# AcquisitionAnalog.net
KiCad netlist of a schematic drawn in Altium Designer
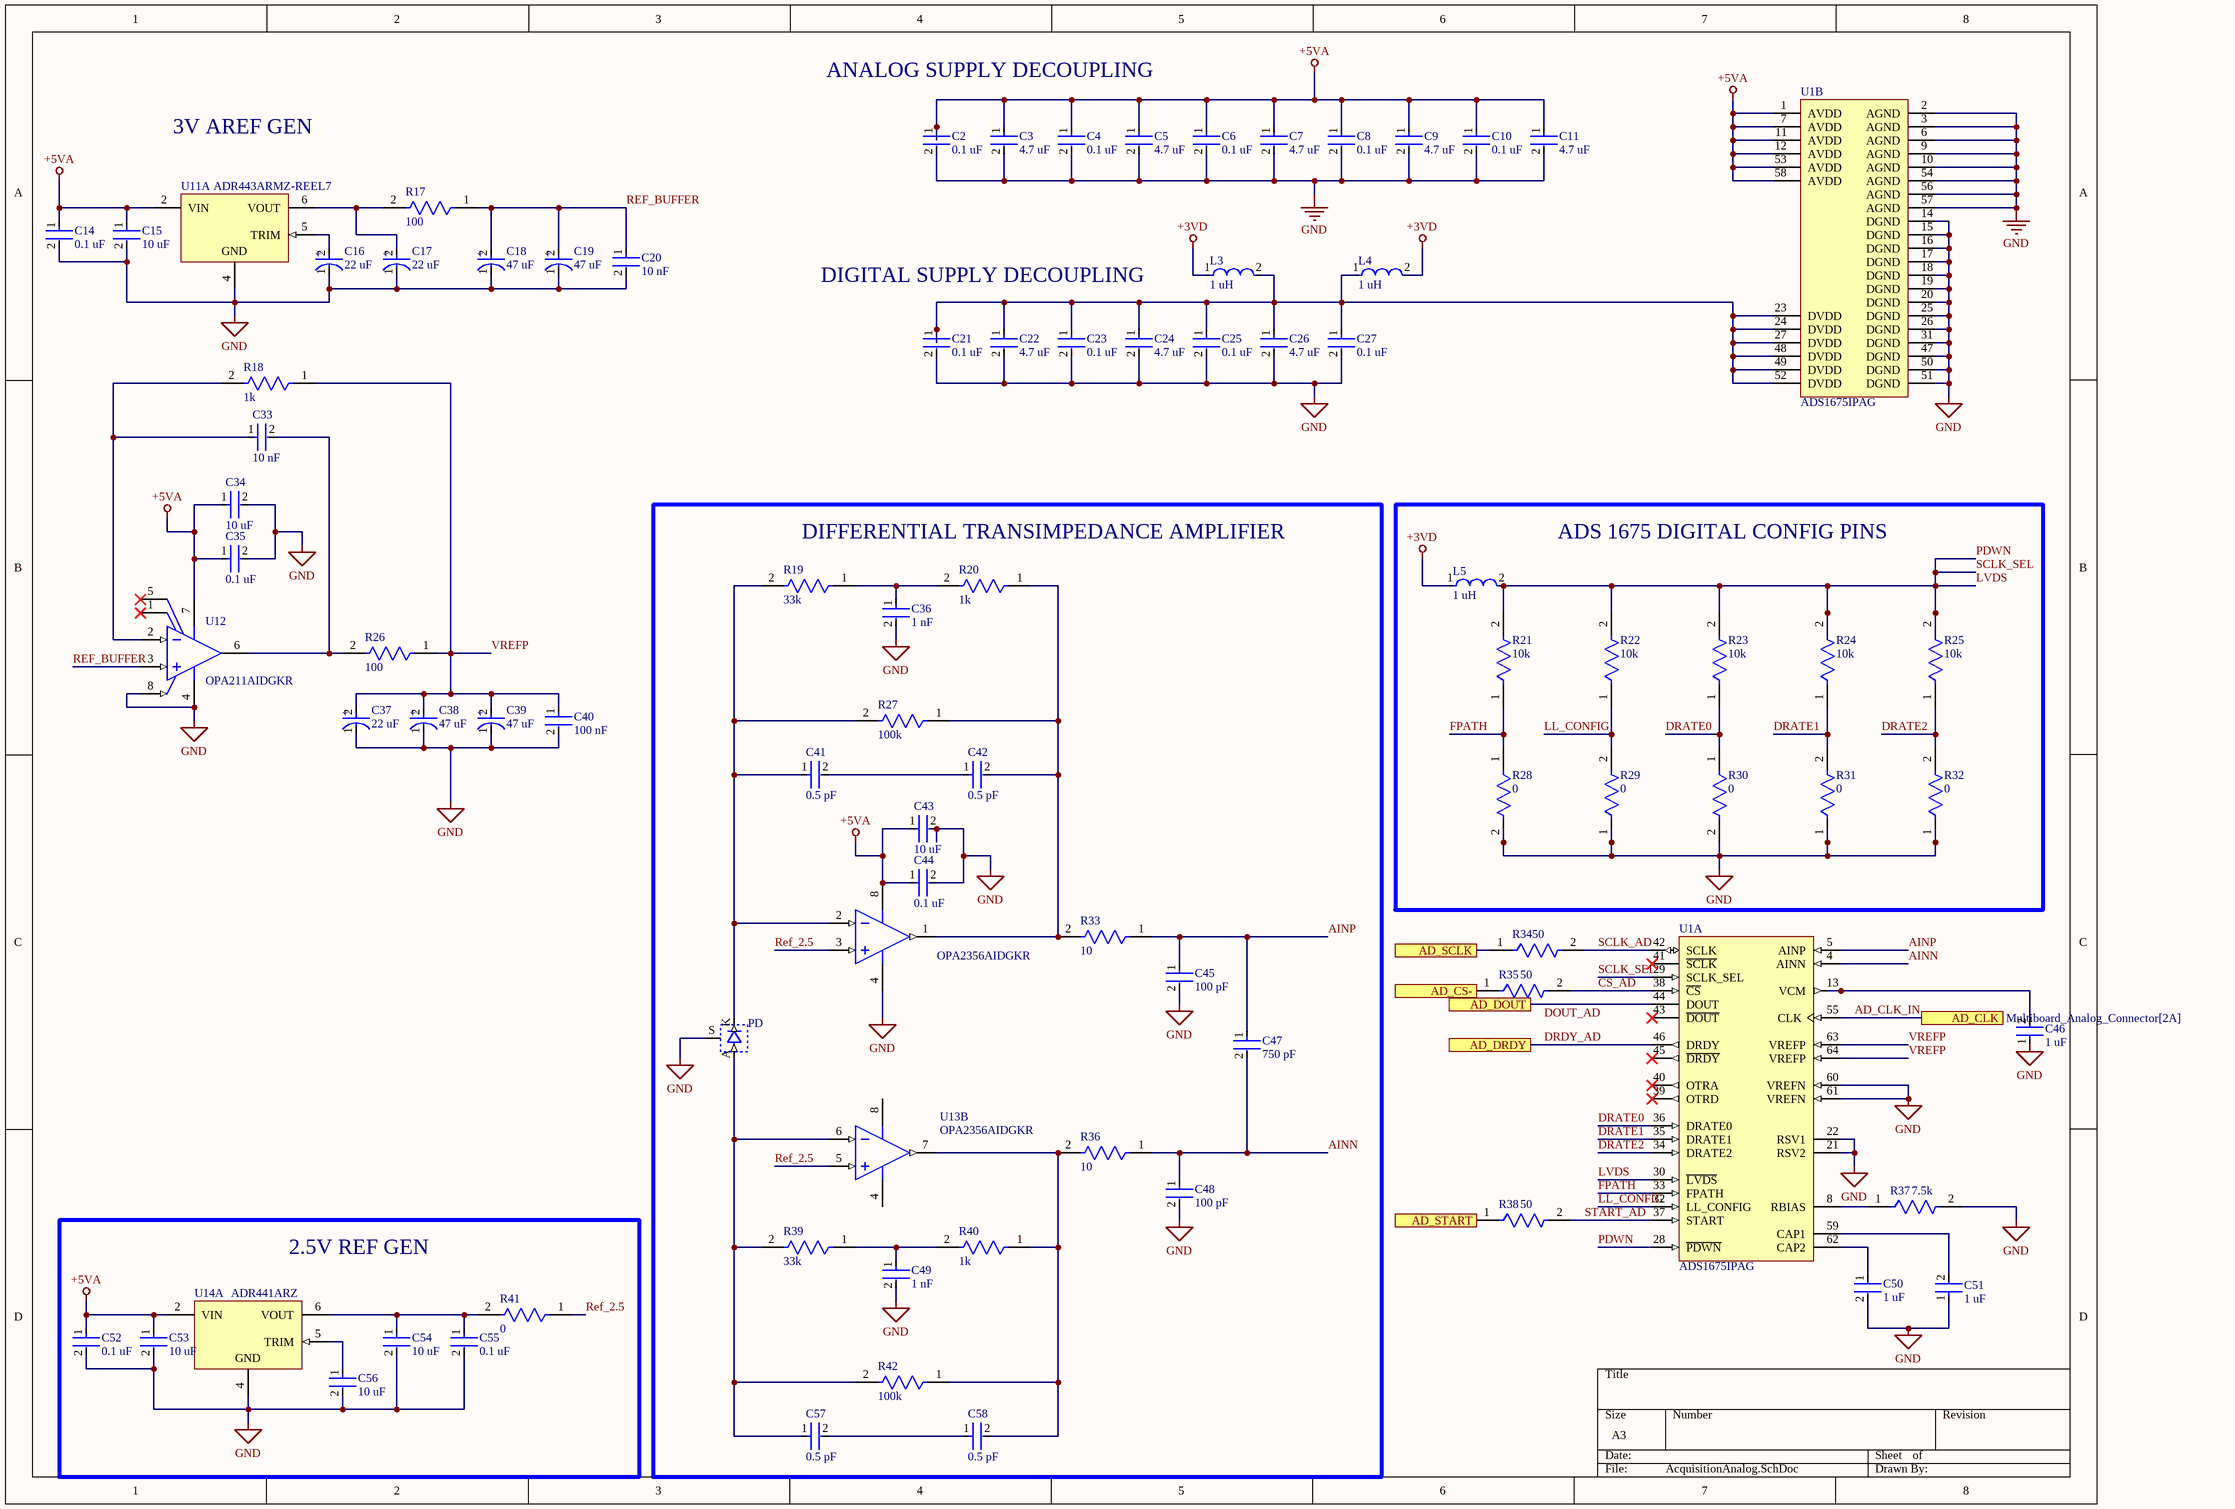
[diagram p0: AcquisitionAnalog.SchDoc]

(export (version "E")
  (design (tool "Eeschema 10.0.6"))
  (components
    (comp (ref "C2")
      (value "0.1 uF")
      (footprint "FP-CC0805-0_85-MFG")
      (description "CAP CER 0.1UF 25V X7R 0805")
      (fields (field (name "MANUFACTURER PART NUMBER") "CC0805KRX7R8BB104") (field (name "TOLERANCE") "0.1"))
      (libsource (lib "Altium Content Vault") (part "11868f565c42a9108669ba33697ecf6"))
    )
    (comp (ref "C3")
      (value "4.7 uF")
      (footprint "FP-CC0805-0_85-MFG")
      (description "CAP CER 0.1UF 25V X7R 0805")
      (fields (field (name "MANUFACTURER PART NUMBER") "CC0805KRX7R8BB104") (field (name "TOLERANCE") "0.1"))
      (libsource (lib "Altium Content Vault") (part "11868f565c42a9108669ba33697ecf6"))
    )
    (comp (ref "C4")
      (value "0.1 uF")
      (footprint "FP-CC0805-0_85-MFG")
      (description "CAP CER 0.1UF 25V X7R 0805")
      (fields (field (name "MANUFACTURER PART NUMBER") "CC0805KRX7R8BB104") (field (name "TOLERANCE") "0.1"))
      (libsource (lib "Altium Content Vault") (part "11868f565c42a9108669ba33697ecf6"))
    )
    (comp (ref "C5")
      (value "4.7 uF")
      (footprint "FP-CC0805-0_85-MFG")
      (description "CAP CER 0.1UF 25V X7R 0805")
      (fields (field (name "MANUFACTURER PART NUMBER") "CC0805KRX7R8BB104") (field (name "TOLERANCE") "0.1"))
      (libsource (lib "Altium Content Vault") (part "11868f565c42a9108669ba33697ecf6"))
    )
    (comp (ref "C6")
      (value "0.1 uF")
      (footprint "FP-CC0805-0_85-MFG")
      (description "CAP CER 0.1UF 25V X7R 0805")
      (fields (field (name "MANUFACTURER PART NUMBER") "CC0805KRX7R8BB104") (field (name "TOLERANCE") "0.1"))
      (libsource (lib "Altium Content Vault") (part "11868f565c42a9108669ba33697ecf6"))
    )
    (comp (ref "C7")
      (value "4.7 uF")
      (footprint "FP-CC0805-0_85-MFG")
      (description "CAP CER 0.1UF 25V X7R 0805")
      (fields (field (name "MANUFACTURER PART NUMBER") "CC0805KRX7R8BB104") (field (name "TOLERANCE") "0.1"))
      (libsource (lib "Altium Content Vault") (part "11868f565c42a9108669ba33697ecf6"))
    )
    (comp (ref "C8")
      (value "0.1 uF")
      (footprint "FP-CC0805-0_85-MFG")
      (description "CAP CER 0.1UF 25V X7R 0805")
      (fields (field (name "MANUFACTURER PART NUMBER") "CC0805KRX7R8BB104") (field (name "TOLERANCE") "0.1"))
      (libsource (lib "Altium Content Vault") (part "11868f565c42a9108669ba33697ecf6"))
    )
    (comp (ref "C9")
      (value "4.7 uF")
      (footprint "FP-CC0805-0_85-MFG")
      (description "CAP CER 0.1UF 25V X7R 0805")
      (fields (field (name "MANUFACTURER PART NUMBER") "CC0805KRX7R8BB104") (field (name "TOLERANCE") "0.1"))
      (libsource (lib "Altium Content Vault") (part "11868f565c42a9108669ba33697ecf6"))
    )
    (comp (ref "C10")
      (value "0.1 uF")
      (footprint "FP-CC0805-0_85-MFG")
      (description "CAP CER 0.1UF 25V X7R 0805")
      (fields (field (name "MANUFACTURER PART NUMBER") "CC0805KRX7R8BB104") (field (name "TOLERANCE") "0.1"))
      (libsource (lib "Altium Content Vault") (part "11868f565c42a9108669ba33697ecf6"))
    )
    (comp (ref "C11")
      (value "4.7 uF")
      (footprint "FP-CC0805-0_85-MFG")
      (description "CAP CER 0.1UF 25V X7R 0805")
      (fields (field (name "MANUFACTURER PART NUMBER") "CC0805KRX7R8BB104") (field (name "TOLERANCE") "0.1"))
      (libsource (lib "Altium Content Vault") (part "11868f565c42a9108669ba33697ecf6"))
    )
    (comp (ref "C14")
      (value "0.1 uF")
      (footprint "FP-CC0805-0_85-MFG")
      (description "CAP CER 0.1UF 25V X7R 0805")
      (fields (field (name "MANUFACTURER PART NUMBER") "CC0805KRX7R8BB104") (field (name "TOLERANCE") "0.1"))
      (libsource (lib "Altium Content Vault") (part "11868f565c42a9108669ba33697ecf6"))
    )
    (comp (ref "C15")
      (value "10 uF")
      (footprint "FP-CC0805-0_85-MFG")
      (description "CAP CER 0.1UF 25V X7R 0805")
      (fields (field (name "MANUFACTURER PART NUMBER") "CC0805KRX7R8BB104") (field (name "TOLERANCE") "0.1"))
      (libsource (lib "Altium Content Vault") (part "11868f565c42a9108669ba33697ecf6"))
    )
    (comp (ref "C16")
      (value "22 uF")
      (footprint "FP-TAJP-MFG")
      (description "10uF 10V  ±20% 6Ω 0805  SMD Tantalum Capacitor")
      (fields (field (name "TOLERANCE") "20%") (field (name "VOLTAGE") "10V"))
      (libsource (lib "Altium Content Vault") (part "a00bbbee19879c290e62620ae7e47b1"))
    )
    (comp (ref "C17")
      (value "22 uF")
      (footprint "FP-TAJP-MFG")
      (description "10uF 10V  ±20% 6Ω 0805  SMD Tantalum Capacitor")
      (fields (field (name "TOLERANCE") "20%") (field (name "VOLTAGE") "10V"))
      (libsource (lib "Altium Content Vault") (part "a00bbbee19879c290e62620ae7e47b1"))
    )
    (comp (ref "C18")
      (value "47 uF")
      (footprint "FP-TAJP-MFG")
      (description "10uF 10V  ±20% 6Ω 0805  SMD Tantalum Capacitor")
      (fields (field (name "TOLERANCE") "20%") (field (name "VOLTAGE") "10V"))
      (libsource (lib "Altium Content Vault") (part "a00bbbee19879c290e62620ae7e47b1"))
    )
    (comp (ref "C19")
      (value "47 uF")
      (footprint "FP-TAJP-MFG")
      (description "10uF 10V  ±20% 6Ω 0805  SMD Tantalum Capacitor")
      (fields (field (name "TOLERANCE") "20%") (field (name "VOLTAGE") "10V"))
      (libsource (lib "Altium Content Vault") (part "a00bbbee19879c290e62620ae7e47b1"))
    )
    (comp (ref "C20")
      (value "10 nF")
      (footprint "FP-CC0805-0_85-MFG")
      (description "CAP CER 0.1UF 25V X7R 0805")
      (fields (field (name "MANUFACTURER PART NUMBER") "CC0805KRX7R8BB104") (field (name "TOLERANCE") "0.1"))
      (libsource (lib "Altium Content Vault") (part "11868f565c42a9108669ba33697ecf6"))
    )
    (comp (ref "C21")
      (value "0.1 uF")
      (footprint "FP-CC0805-0_85-MFG")
      (description "CAP CER 0.1UF 25V X7R 0805")
      (fields (field (name "MANUFACTURER PART NUMBER") "CC0805KRX7R8BB104") (field (name "TOLERANCE") "0.1"))
      (libsource (lib "Altium Content Vault") (part "11868f565c42a9108669ba33697ecf6"))
    )
    (comp (ref "C22")
      (value "4.7 uF")
      (footprint "FP-CC0805-0_85-MFG")
      (description "CAP CER 0.1UF 25V X7R 0805")
      (fields (field (name "MANUFACTURER PART NUMBER") "CC0805KRX7R8BB104") (field (name "TOLERANCE") "0.1"))
      (libsource (lib "Altium Content Vault") (part "11868f565c42a9108669ba33697ecf6"))
    )
    (comp (ref "C23")
      (value "0.1 uF")
      (footprint "FP-CC0805-0_85-MFG")
      (description "CAP CER 0.1UF 25V X7R 0805")
      (fields (field (name "MANUFACTURER PART NUMBER") "CC0805KRX7R8BB104") (field (name "TOLERANCE") "0.1"))
      (libsource (lib "Altium Content Vault") (part "11868f565c42a9108669ba33697ecf6"))
    )
    (comp (ref "C24")
      (value "4.7 uF")
      (footprint "FP-CC0805-0_85-MFG")
      (description "CAP CER 0.1UF 25V X7R 0805")
      (fields (field (name "MANUFACTURER PART NUMBER") "CC0805KRX7R8BB104") (field (name "TOLERANCE") "0.1"))
      (libsource (lib "Altium Content Vault") (part "11868f565c42a9108669ba33697ecf6"))
    )
    (comp (ref "C25")
      (value "0.1 uF")
      (footprint "FP-CC0805-0_85-MFG")
      (description "CAP CER 0.1UF 25V X7R 0805")
      (fields (field (name "MANUFACTURER PART NUMBER") "CC0805KRX7R8BB104") (field (name "TOLERANCE") "0.1"))
      (libsource (lib "Altium Content Vault") (part "11868f565c42a9108669ba33697ecf6"))
    )
    (comp (ref "C26")
      (value "4.7 uF")
      (footprint "FP-CC0805-0_85-MFG")
      (description "CAP CER 0.1UF 25V X7R 0805")
      (fields (field (name "MANUFACTURER PART NUMBER") "CC0805KRX7R8BB104") (field (name "TOLERANCE") "0.1"))
      (libsource (lib "Altium Content Vault") (part "11868f565c42a9108669ba33697ecf6"))
    )
    (comp (ref "C27")
      (value "0.1 uF")
      (footprint "FP-CC0805-0_85-MFG")
      (description "CAP CER 0.1UF 25V X7R 0805")
      (fields (field (name "MANUFACTURER PART NUMBER") "CC0805KRX7R8BB104") (field (name "TOLERANCE") "0.1"))
      (libsource (lib "Altium Content Vault") (part "11868f565c42a9108669ba33697ecf6"))
    )
    (comp (ref "C33")
      (value "10 nF")
      (footprint "FP-CC0805-0_85-MFG")
      (description "CAP CER 0.1UF 25V X7R 0805")
      (fields (field (name "MANUFACTURER PART NUMBER") "CC0805KRX7R8BB104") (field (name "TOLERANCE") "0.1"))
      (libsource (lib "Altium Content Vault") (part "11868f565c42a9108669ba33697ecf6"))
    )
    (comp (ref "C34")
      (value "10 uF")
      (footprint "FP-CC0805-0_85-MFG")
      (description "CAP CER 0.1UF 25V X7R 0805")
      (fields (field (name "MANUFACTURER PART NUMBER") "CC0805KRX7R8BB104") (field (name "TOLERANCE") "0.1"))
      (libsource (lib "Altium Content Vault") (part "11868f565c42a9108669ba33697ecf6"))
    )
    (comp (ref "C35")
      (value "0.1 uF")
      (footprint "FP-CC0805-0_85-MFG")
      (description "CAP CER 0.1UF 25V X7R 0805")
      (fields (field (name "MANUFACTURER PART NUMBER") "CC0805KRX7R8BB104") (field (name "TOLERANCE") "0.1"))
      (libsource (lib "Altium Content Vault") (part "11868f565c42a9108669ba33697ecf6"))
    )
    (comp (ref "C36")
      (value "1 nF")
      (footprint "FP-CC0805-0_85-MFG")
      (description "CAP CER 0.1UF 25V X7R 0805")
      (fields (field (name "MANUFACTURER PART NUMBER") "CC0805KRX7R8BB104") (field (name "TOLERANCE") "0.1"))
      (libsource (lib "Altium Content Vault") (part "11868f565c42a9108669ba33697ecf6"))
    )
    (comp (ref "C37")
      (value "22 uF")
      (footprint "FP-TAJP-MFG")
      (description "10uF 10V  ±20% 6Ω 0805  SMD Tantalum Capacitor")
      (fields (field (name "TOLERANCE") "20%") (field (name "VOLTAGE") "10V"))
      (libsource (lib "Altium Content Vault") (part "a00bbbee19879c290e62620ae7e47b1"))
    )
    (comp (ref "C38")
      (value "47 uF")
      (footprint "FP-TAJP-MFG")
      (description "10uF 10V  ±20% 6Ω 0805  SMD Tantalum Capacitor")
      (fields (field (name "TOLERANCE") "20%") (field (name "VOLTAGE") "10V"))
      (libsource (lib "Altium Content Vault") (part "a00bbbee19879c290e62620ae7e47b1"))
    )
    (comp (ref "C39")
      (value "47 uF")
      (footprint "FP-TAJP-MFG")
      (description "10uF 10V  ±20% 6Ω 0805  SMD Tantalum Capacitor")
      (fields (field (name "TOLERANCE") "20%") (field (name "VOLTAGE") "10V"))
      (libsource (lib "Altium Content Vault") (part "a00bbbee19879c290e62620ae7e47b1"))
    )
    (comp (ref "C40")
      (value "100 nF")
      (footprint "FP-CC0805-0_85-MFG")
      (description "CAP CER 0.1UF 25V X7R 0805")
      (fields (field (name "MANUFACTURER PART NUMBER") "CC0805KRX7R8BB104") (field (name "TOLERANCE") "0.1"))
      (libsource (lib "Altium Content Vault") (part "11868f565c42a9108669ba33697ecf6"))
    )
    (comp (ref "C41")
      (value "0.5 pF")
      (footprint "FP-CC0805-0_85-MFG")
      (description "CAP CER 0.1UF 25V X7R 0805")
      (fields (field (name "MANUFACTURER PART NUMBER") "CC0805KRX7R8BB104") (field (name "TOLERANCE") "0.1"))
      (libsource (lib "Altium Content Vault") (part "11868f565c42a9108669ba33697ecf6"))
    )
    (comp (ref "C42")
      (value "0.5 pF")
      (footprint "FP-CC0805-0_85-MFG")
      (description "CAP CER 0.1UF 25V X7R 0805")
      (fields (field (name "MANUFACTURER PART NUMBER") "CC0805KRX7R8BB104") (field (name "TOLERANCE") "0.1"))
      (libsource (lib "Altium Content Vault") (part "11868f565c42a9108669ba33697ecf6"))
    )
    (comp (ref "C43")
      (value "10 uF")
      (footprint "FP-CC0805-0_85-MFG")
      (description "CAP CER 0.1UF 25V X7R 0805")
      (fields (field (name "MANUFACTURER PART NUMBER") "CC0805KRX7R8BB104") (field (name "TOLERANCE") "0.1"))
      (libsource (lib "Altium Content Vault") (part "11868f565c42a9108669ba33697ecf6"))
    )
    (comp (ref "C44")
      (value "0.1 uF")
      (footprint "FP-CC0805-0_85-MFG")
      (description "CAP CER 0.1UF 25V X7R 0805")
      (fields (field (name "MANUFACTURER PART NUMBER") "CC0805KRX7R8BB104") (field (name "TOLERANCE") "0.1"))
      (libsource (lib "Altium Content Vault") (part "11868f565c42a9108669ba33697ecf6"))
    )
    (comp (ref "C45")
      (value "100 pF")
      (footprint "FP-CC0805-0_85-MFG")
      (description "CAP CER 0.1UF 25V X7R 0805")
      (fields (field (name "MANUFACTURER PART NUMBER") "CC0805KRX7R8BB104") (field (name "TOLERANCE") "0.1"))
      (libsource (lib "Altium Content Vault") (part "11868f565c42a9108669ba33697ecf6"))
    )
    (comp (ref "C46")
      (value "1 uF")
      (footprint "FP-CC0805-0_85-MFG")
      (description "CAP CER 0.1UF 25V X7R 0805")
      (fields (field (name "MANUFACTURER PART NUMBER") "CC0805KRX7R8BB104") (field (name "TOLERANCE") "0.1"))
      (libsource (lib "Altium Content Vault") (part "11868f565c42a9108669ba33697ecf6"))
    )
    (comp (ref "C47")
      (value "750 pF")
      (footprint "FP-CC0805-0_85-MFG")
      (description "CAP CER 0.1UF 25V X7R 0805")
      (fields (field (name "MANUFACTURER PART NUMBER") "CC0805KRX7R8BB104") (field (name "TOLERANCE") "0.1"))
      (libsource (lib "Altium Content Vault") (part "11868f565c42a9108669ba33697ecf6"))
    )
    (comp (ref "C48")
      (value "100 pF")
      (footprint "FP-CC0805-0_85-MFG")
      (description "CAP CER 0.1UF 25V X7R 0805")
      (fields (field (name "MANUFACTURER PART NUMBER") "CC0805KRX7R8BB104") (field (name "TOLERANCE") "0.1"))
      (libsource (lib "Altium Content Vault") (part "11868f565c42a9108669ba33697ecf6"))
    )
    (comp (ref "C49")
      (value "1 nF")
      (footprint "FP-CC0805-0_85-MFG")
      (description "CAP CER 0.1UF 25V X7R 0805")
      (fields (field (name "MANUFACTURER PART NUMBER") "CC0805KRX7R8BB104") (field (name "TOLERANCE") "0.1"))
      (libsource (lib "Altium Content Vault") (part "11868f565c42a9108669ba33697ecf6"))
    )
    (comp (ref "C50")
      (value "1 uF")
      (footprint "FP-CC0805-0_85-MFG")
      (description "CAP CER 0.1UF 25V X7R 0805")
      (fields (field (name "MANUFACTURER PART NUMBER") "CC0805KRX7R8BB104") (field (name "TOLERANCE") "0.1"))
      (libsource (lib "Altium Content Vault") (part "11868f565c42a9108669ba33697ecf6"))
    )
    (comp (ref "C51")
      (value "1 uF")
      (footprint "FP-CC0805-0_85-MFG")
      (description "CAP CER 0.1UF 25V X7R 0805")
      (fields (field (name "MANUFACTURER PART NUMBER") "CC0805KRX7R8BB104") (field (name "TOLERANCE") "0.1"))
      (libsource (lib "Altium Content Vault") (part "11868f565c42a9108669ba33697ecf6"))
    )
    (comp (ref "C52")
      (value "0.1 uF")
      (footprint "FP-CC0805-0_85-MFG")
      (description "CAP CER 0.1UF 25V X7R 0805")
      (fields (field (name "MANUFACTURER PART NUMBER") "CC0805KRX7R8BB104") (field (name "TOLERANCE") "0.1"))
      (libsource (lib "Altium Content Vault") (part "11868f565c42a9108669ba33697ecf6"))
    )
    (comp (ref "C53")
      (value "10 uF")
      (footprint "FP-CC0805-0_85-MFG")
      (description "CAP CER 0.1UF 25V X7R 0805")
      (fields (field (name "MANUFACTURER PART NUMBER") "CC0805KRX7R8BB104") (field (name "TOLERANCE") "0.1"))
      (libsource (lib "Altium Content Vault") (part "11868f565c42a9108669ba33697ecf6"))
    )
    (comp (ref "C54")
      (value "10 uF")
      (footprint "FP-CC0805-0_85-MFG")
      (description "CAP CER 0.1UF 25V X7R 0805")
      (fields (field (name "MANUFACTURER PART NUMBER") "CC0805KRX7R8BB104") (field (name "TOLERANCE") "0.1"))
      (libsource (lib "Altium Content Vault") (part "11868f565c42a9108669ba33697ecf6"))
    )
    (comp (ref "C55")
      (value "0.1 uF")
      (footprint "FP-CC0805-0_85-MFG")
      (description "CAP CER 0.1UF 25V X7R 0805")
      (fields (field (name "MANUFACTURER PART NUMBER") "CC0805KRX7R8BB104") (field (name "TOLERANCE") "0.1"))
      (libsource (lib "Altium Content Vault") (part "11868f565c42a9108669ba33697ecf6"))
    )
    (comp (ref "C56")
      (value "10 uF")
      (footprint "FP-CC0805-0_85-MFG")
      (description "CAP CER 0.1UF 25V X7R 0805")
      (fields (field (name "MANUFACTURER PART NUMBER") "CC0805KRX7R8BB104") (field (name "TOLERANCE") "0.1"))
      (libsource (lib "Altium Content Vault") (part "11868f565c42a9108669ba33697ecf6"))
    )
    (comp (ref "C57")
      (value "0.5 pF")
      (footprint "FP-CC0805-0_85-MFG")
      (description "CAP CER 0.1UF 25V X7R 0805")
      (fields (field (name "MANUFACTURER PART NUMBER") "CC0805KRX7R8BB104") (field (name "TOLERANCE") "0.1"))
      (libsource (lib "Altium Content Vault") (part "11868f565c42a9108669ba33697ecf6"))
    )
    (comp (ref "C58")
      (value "0.5 pF")
      (footprint "FP-CC0805-0_85-MFG")
      (description "CAP CER 0.1UF 25V X7R 0805")
      (fields (field (name "MANUFACTURER PART NUMBER") "CC0805KRX7R8BB104") (field (name "TOLERANCE") "0.1"))
      (libsource (lib "Altium Content Vault") (part "11868f565c42a9108669ba33697ecf6"))
    )
    (comp (ref "L3")
      (value "1 uH")
      (footprint "FP-LQM21DN_00-IPC_B")
      (description "Multilayer Type Inductor for General Circuits, 0805 (2012), 1μH, 10%, 0.4Ω, 50mA")
      (fields (field (name "TOLERANCE") "10%"))
      (libsource (lib "Altium Content Vault") (part "725321dda6339637d4d059423bc1c3c"))
    )
    (comp (ref "L4")
      (value "1 uH")
      (footprint "FP-LQM21DN_00-IPC_B")
      (description "Multilayer Type Inductor for General Circuits, 0805 (2012), 1μH, 10%, 0.4Ω, 50mA")
      (fields (field (name "TOLERANCE") "10%"))
      (libsource (lib "Altium Content Vault") (part "725321dda6339637d4d059423bc1c3c"))
    )
    (comp (ref "L5")
      (value "1 uH")
      (footprint "FP-LQM21DN_00-IPC_B")
      (description "Multilayer Type Inductor for General Circuits, 0805 (2012), 1μH, 10%, 0.4Ω, 50mA")
      (fields (field (name "TOLERANCE") "10%"))
      (libsource (lib "Altium Content Vault") (part "725321dda6339637d4d059423bc1c3c"))
    )
    (comp (ref "PD") (value "~") (footprint "otico") (libsource (lib "New Gyro 4.0") (part "BYW29-150")))
    (comp (ref "R17")
      (value "100")
      (footprint "FP-RR1220-MFG")
      (description "49.9Ω ±0.5% 0.1W 1/10W Chip Resistor 0805 (2012 Metric) Thin Film")
      (fields (field (name "TOLERANCE") "0.5%"))
      (libsource (lib "Altium Content Vault") (part "1029c3af85768c4190bb7ad29bc67b5"))
    )
    (comp (ref "R18")
      (value "1k")
      (footprint "FP-RR1220-MFG")
      (description "49.9Ω ±0.5% 0.1W 1/10W Chip Resistor 0805 (2012 Metric) Thin Film")
      (fields (field (name "TOLERANCE") "0.5%"))
      (libsource (lib "Altium Content Vault") (part "1029c3af85768c4190bb7ad29bc67b5"))
    )
    (comp (ref "R19")
      (value "33k")
      (footprint "FP-RR1220-MFG")
      (description "49.9Ω ±0.5% 0.1W 1/10W Chip Resistor 0805 (2012 Metric) Thin Film")
      (fields (field (name "TOLERANCE") "0.5%"))
      (libsource (lib "Altium Content Vault") (part "1029c3af85768c4190bb7ad29bc67b5"))
    )
    (comp (ref "R20")
      (value "1k")
      (footprint "FP-RR1220-MFG")
      (description "49.9Ω ±0.5% 0.1W 1/10W Chip Resistor 0805 (2012 Metric) Thin Film")
      (fields (field (name "TOLERANCE") "0.5%"))
      (libsource (lib "Altium Content Vault") (part "1029c3af85768c4190bb7ad29bc67b5"))
    )
    (comp (ref "R21")
      (value "10k")
      (footprint "FP-RR1220-MFG")
      (description "49.9Ω ±0.5% 0.1W 1/10W Chip Resistor 0805 (2012 Metric) Thin Film")
      (fields (field (name "TOLERANCE") "0.5%"))
      (libsource (lib "Altium Content Vault") (part "1029c3af85768c4190bb7ad29bc67b5"))
    )
    (comp (ref "R22")
      (value "10k")
      (footprint "FP-RR1220-MFG")
      (description "49.9Ω ±0.5% 0.1W 1/10W Chip Resistor 0805 (2012 Metric) Thin Film")
      (fields (field (name "TOLERANCE") "0.5%"))
      (libsource (lib "Altium Content Vault") (part "1029c3af85768c4190bb7ad29bc67b5"))
    )
    (comp (ref "R23")
      (value "10k")
      (footprint "FP-RR1220-MFG")
      (description "49.9Ω ±0.5% 0.1W 1/10W Chip Resistor 0805 (2012 Metric) Thin Film")
      (fields (field (name "TOLERANCE") "0.5%"))
      (libsource (lib "Altium Content Vault") (part "1029c3af85768c4190bb7ad29bc67b5"))
    )
    (comp (ref "R24")
      (value "10k")
      (footprint "FP-RR1220-MFG")
      (description "49.9Ω ±0.5% 0.1W 1/10W Chip Resistor 0805 (2012 Metric) Thin Film")
      (fields (field (name "TOLERANCE") "0.5%"))
      (libsource (lib "Altium Content Vault") (part "1029c3af85768c4190bb7ad29bc67b5"))
    )
    (comp (ref "R25")
      (value "10k")
      (footprint "FP-RR1220-MFG")
      (description "49.9Ω ±0.5% 0.1W 1/10W Chip Resistor 0805 (2012 Metric) Thin Film")
      (fields (field (name "TOLERANCE") "0.5%"))
      (libsource (lib "Altium Content Vault") (part "1029c3af85768c4190bb7ad29bc67b5"))
    )
    (comp (ref "R26")
      (value "100")
      (footprint "FP-RR1220-MFG")
      (description "49.9Ω ±0.5% 0.1W 1/10W Chip Resistor 0805 (2012 Metric) Thin Film")
      (fields (field (name "TOLERANCE") "0.5%"))
      (libsource (lib "Altium Content Vault") (part "1029c3af85768c4190bb7ad29bc67b5"))
    )
    (comp (ref "R27")
      (value "100k")
      (footprint "FP-RR1220-MFG")
      (description "49.9Ω ±0.5% 0.1W 1/10W Chip Resistor 0805 (2012 Metric) Thin Film")
      (fields (field (name "TOLERANCE") "0.5%"))
      (libsource (lib "Altium Content Vault") (part "1029c3af85768c4190bb7ad29bc67b5"))
    )
    (comp (ref "R28")
      (value "0")
      (footprint "FP-RR1220-MFG")
      (description "49.9Ω ±0.5% 0.1W 1/10W Chip Resistor 0805 (2012 Metric) Thin Film")
      (fields (field (name "TOLERANCE") "0.5%"))
      (libsource (lib "Altium Content Vault") (part "1029c3af85768c4190bb7ad29bc67b5"))
    )
    (comp (ref "R29")
      (value "0")
      (footprint "FP-RR1220-MFG")
      (description "49.9Ω ±0.5% 0.1W 1/10W Chip Resistor 0805 (2012 Metric) Thin Film")
      (fields (field (name "TOLERANCE") "0.5%"))
      (libsource (lib "Altium Content Vault") (part "1029c3af85768c4190bb7ad29bc67b5"))
    )
    (comp (ref "R30")
      (value "0")
      (footprint "FP-RR1220-MFG")
      (description "49.9Ω ±0.5% 0.1W 1/10W Chip Resistor 0805 (2012 Metric) Thin Film")
      (fields (field (name "TOLERANCE") "0.5%"))
      (libsource (lib "Altium Content Vault") (part "1029c3af85768c4190bb7ad29bc67b5"))
    )
    (comp (ref "R31")
      (value "0")
      (footprint "FP-RR1220-MFG")
      (description "49.9Ω ±0.5% 0.1W 1/10W Chip Resistor 0805 (2012 Metric) Thin Film")
      (fields (field (name "TOLERANCE") "0.5%"))
      (libsource (lib "Altium Content Vault") (part "1029c3af85768c4190bb7ad29bc67b5"))
    )
    (comp (ref "R32")
      (value "0")
      (footprint "FP-RR1220-MFG")
      (description "49.9Ω ±0.5% 0.1W 1/10W Chip Resistor 0805 (2012 Metric) Thin Film")
      (fields (field (name "TOLERANCE") "0.5%"))
      (libsource (lib "Altium Content Vault") (part "1029c3af85768c4190bb7ad29bc67b5"))
    )
    (comp (ref "R33")
      (value "10")
      (footprint "FP-RR1220-MFG")
      (description "49.9Ω ±0.5% 0.1W 1/10W Chip Resistor 0805 (2012 Metric) Thin Film")
      (fields (field (name "TOLERANCE") "0.5%"))
      (libsource (lib "Altium Content Vault") (part "1029c3af85768c4190bb7ad29bc67b5"))
    )
    (comp (ref "R34")
      (value "50")
      (footprint "FP-RR1220-MFG")
      (description "49.9Ω ±0.5% 0.1W 1/10W Chip Resistor 0805 (2012 Metric) Thin Film")
      (fields (field (name "TOLERANCE") "0.5%"))
      (libsource (lib "Altium Content Vault") (part "1029c3af85768c4190bb7ad29bc67b5"))
    )
    (comp (ref "R35")
      (value "50")
      (footprint "FP-RR1220-MFG")
      (description "49.9Ω ±0.5% 0.1W 1/10W Chip Resistor 0805 (2012 Metric) Thin Film")
      (fields (field (name "TOLERANCE") "0.5%"))
      (libsource (lib "Altium Content Vault") (part "1029c3af85768c4190bb7ad29bc67b5"))
    )
    (comp (ref "R36")
      (value "10")
      (footprint "FP-RR1220-MFG")
      (description "49.9Ω ±0.5% 0.1W 1/10W Chip Resistor 0805 (2012 Metric) Thin Film")
      (fields (field (name "TOLERANCE") "0.5%"))
      (libsource (lib "Altium Content Vault") (part "1029c3af85768c4190bb7ad29bc67b5"))
    )
    (comp (ref "R37")
      (value "7.5k")
      (footprint "FP-RR1220-MFG")
      (description "49.9Ω ±0.5% 0.1W 1/10W Chip Resistor 0805 (2012 Metric) Thin Film")
      (fields (field (name "TOLERANCE") "0.5%"))
      (libsource (lib "Altium Content Vault") (part "1029c3af85768c4190bb7ad29bc67b5"))
    )
    (comp (ref "R38")
      (value "50")
      (footprint "FP-RR1220-MFG")
      (description "49.9Ω ±0.5% 0.1W 1/10W Chip Resistor 0805 (2012 Metric) Thin Film")
      (fields (field (name "TOLERANCE") "0.5%"))
      (libsource (lib "Altium Content Vault") (part "1029c3af85768c4190bb7ad29bc67b5"))
    )
    (comp (ref "R39")
      (value "33k")
      (footprint "FP-RR1220-MFG")
      (description "49.9Ω ±0.5% 0.1W 1/10W Chip Resistor 0805 (2012 Metric) Thin Film")
      (fields (field (name "TOLERANCE") "0.5%"))
      (libsource (lib "Altium Content Vault") (part "1029c3af85768c4190bb7ad29bc67b5"))
    )
    (comp (ref "R40")
      (value "1k")
      (footprint "FP-RR1220-MFG")
      (description "49.9Ω ±0.5% 0.1W 1/10W Chip Resistor 0805 (2012 Metric) Thin Film")
      (fields (field (name "TOLERANCE") "0.5%"))
      (libsource (lib "Altium Content Vault") (part "1029c3af85768c4190bb7ad29bc67b5"))
    )
    (comp (ref "R41")
      (value "0")
      (footprint "FP-RR1220-MFG")
      (description "49.9Ω ±0.5% 0.1W 1/10W Chip Resistor 0805 (2012 Metric) Thin Film")
      (fields (field (name "TOLERANCE") "0.5%"))
      (libsource (lib "Altium Content Vault") (part "1029c3af85768c4190bb7ad29bc67b5"))
    )
    (comp (ref "R42")
      (value "100k")
      (footprint "FP-RR1220-MFG")
      (description "49.9Ω ±0.5% 0.1W 1/10W Chip Resistor 0805 (2012 Metric) Thin Film")
      (fields (field (name "TOLERANCE") "0.5%"))
      (libsource (lib "Altium Content Vault") (part "1029c3af85768c4190bb7ad29bc67b5"))
    )
    (comp (ref "U1")
      (value "ADS1675IPAG")
      (footprint "TI-PAG64_L")
      (description "4 MSPS, 24-Bit ADC, -40 to 85 degC, 64-pin QFP (PAG64), Green (RoHS & no Sb/Br)")
      (fields (field (name "MANUFACTURER") "Texas Instruments"))
      (libsource (lib "Altium Content Vault") (part "TI-ADS1675PAG64"))
    )
    (comp (ref "U11")
      (value "ADR443ARMZ-REEL7")
      (footprint "ADI-RM-8_L")
      (fields (field (name "MANUFACTURER") "Analog Devices"))
      (libsource (lib "Altium Content Vault") (part "ADI-ADR4XX-8"))
    )
    (comp (ref "U12")
      (value "OPA211AIDGKR")
      (footprint "DGK0008A_M")
      (fields (field (name "MANUFACTURER") "Texas Instruments"))
      (libsource (lib "Altium Content Vault") (part "TI-OPA211-XX-DGK8"))
    )
    (comp (ref "U13")
      (value "OPA2356AIDGKR")
      (footprint "DGK0008A_M")
      (fields (field (name "MANUFACTURER") "Texas Instruments"))
      (libsource (lib "Altium Content Vault") (part "TI-OPA2356DGK8"))
    )
    (comp (ref "U14")
      (value "ADR441ARZ")
      (footprint "ADI-R-8_L")
      (fields (field (name "MANUFACTURER") "Analog Devices"))
      (libsource (lib "Altium Content Vault") (part "ADI-ADR4XX-8"))
    )
  )
  (nets
    (net (code "1") (name "+3VD") (class "Default")
      (node (ref "L3") (pin "1") (pinfunction "1_1") (pintype "passive"))
      (node (ref "L4") (pin "2") (pinfunction "2_2") (pintype "passive"))
      (node (ref "L5") (pin "1") (pinfunction "1_1") (pintype "passive"))
    )
    (net (code "2") (name "+5VA") (class "Default")
      (node (ref "C10") (pin "1") (pinfunction "1_1") (pintype "passive"))
      (node (ref "C11") (pin "1") (pinfunction "1_1") (pintype "passive"))
      (node (ref "C14") (pin "1") (pinfunction "1_1") (pintype "passive"))
      (node (ref "C15") (pin "1") (pinfunction "1_1") (pintype "passive"))
      (node (ref "C2") (pin "1") (pinfunction "1_1") (pintype "passive"))
      (node (ref "C3") (pin "1") (pinfunction "1_1") (pintype "passive"))
      (node (ref "C34") (pin "1") (pinfunction "1_1") (pintype "passive"))
      (node (ref "C35") (pin "1") (pinfunction "1_1") (pintype "passive"))
      (node (ref "C4") (pin "1") (pinfunction "1_1") (pintype "passive"))
      (node (ref "C43") (pin "1") (pinfunction "1_1") (pintype "passive"))
      (node (ref "C44") (pin "1") (pinfunction "1_1") (pintype "passive"))
      (node (ref "C5") (pin "1") (pinfunction "1_1") (pintype "passive"))
      (node (ref "C52") (pin "1") (pinfunction "1_1") (pintype "passive"))
      (node (ref "C53") (pin "1") (pinfunction "1_1") (pintype "passive"))
      (node (ref "C6") (pin "1") (pinfunction "1_1") (pintype "passive"))
      (node (ref "C7") (pin "1") (pinfunction "1_1") (pintype "passive"))
      (node (ref "C8") (pin "1") (pinfunction "1_1") (pintype "passive"))
      (node (ref "C9") (pin "1") (pinfunction "1_1") (pintype "passive"))
      (node (ref "U1") (pin "1") (pinfunction "AVDD_1") (pintype "power_in"))
      (node (ref "U1") (pin "11") (pinfunction "AVDD_11") (pintype "power_in"))
      (node (ref "U1") (pin "12") (pinfunction "AVDD_12") (pintype "power_in"))
      (node (ref "U1") (pin "53") (pinfunction "AVDD_53") (pintype "power_in"))
      (node (ref "U1") (pin "58") (pinfunction "AVDD_58") (pintype "power_in"))
      (node (ref "U1") (pin "7") (pinfunction "AVDD_7") (pintype "power_in"))
      (node (ref "U11") (pin "2") (pinfunction "VIN_2") (pintype "power_in"))
      (node (ref "U12") (pin "7") (pinfunction "V+_7") (pintype "power_in"))
      (node (ref "U13") (pin "8") (pinfunction "V+_8") (pintype "power_in"))
      (node (ref "U14") (pin "2") (pinfunction "VIN_2") (pintype "power_in"))
    )
    (net (code "3") (name "/AD_CLK_IN") (class "Default")
      (node (ref "U1") (pin "55") (pinfunction "CLK_55") (pintype "input"))
    )
    (net (code "4") (name "/AD_CS-") (class "Default")
      (node (ref "R35") (pin "1") (pinfunction "1_1") (pintype "passive"))
    )
    (net (code "5") (name "/AD_SCLK") (class "Default")
      (node (ref "R34") (pin "1") (pinfunction "1_1") (pintype "passive"))
    )
    (net (code "6") (name "/AD_START") (class "Default")
      (node (ref "R38") (pin "1") (pinfunction "1_1") (pintype "passive"))
    )
    (net (code "7") (name "/AINN") (class "Default")
      (node (ref "C47") (pin "2") (pinfunction "2_2") (pintype "passive"))
      (node (ref "C48") (pin "1") (pinfunction "1_1") (pintype "passive"))
      (node (ref "R36") (pin "1") (pinfunction "1_1") (pintype "passive"))
      (node (ref "U1") (pin "4") (pinfunction "AINN_4") (pintype "input"))
    )
    (net (code "8") (name "/AINP") (class "Default")
      (node (ref "C45") (pin "1") (pinfunction "1_1") (pintype "passive"))
      (node (ref "C47") (pin "1") (pinfunction "1_1") (pintype "passive"))
      (node (ref "R33") (pin "1") (pinfunction "1_1") (pintype "passive"))
      (node (ref "U1") (pin "5") (pinfunction "AINP_5") (pintype "input"))
    )
    (net (code "9") (name "/CS_AD") (class "Default")
      (node (ref "R35") (pin "2") (pinfunction "2_2") (pintype "passive"))
      (node (ref "U1") (pin "38") (pinfunction "~{CS}_38") (pintype "input"))
    )
    (net (code "10") (name "/DOUT_AD") (class "Default")
      (node (ref "U1") (pin "44") (pinfunction "DOUT_44") (pintype "tri_state"))
    )
    (net (code "11") (name "/DRATE0") (class "Default")
      (node (ref "R23") (pin "1") (pinfunction "1_1") (pintype "passive"))
      (node (ref "R30") (pin "1") (pinfunction "1_1") (pintype "passive"))
      (node (ref "U1") (pin "36") (pinfunction "DRATE0_36") (pintype "input"))
    )
    (net (code "12") (name "/DRATE1") (class "Default")
      (node (ref "R24") (pin "1") (pinfunction "1_1") (pintype "passive"))
      (node (ref "R31") (pin "2") (pinfunction "2_2") (pintype "passive"))
      (node (ref "U1") (pin "35") (pinfunction "DRATE1_35") (pintype "input"))
    )
    (net (code "13") (name "/DRATE2") (class "Default")
      (node (ref "R25") (pin "1") (pinfunction "1_1") (pintype "passive"))
      (node (ref "R32") (pin "2") (pinfunction "2_2") (pintype "passive"))
      (node (ref "U1") (pin "34") (pinfunction "DRATE2_34") (pintype "input"))
    )
    (net (code "14") (name "/DRDY_AD") (class "Default")
      (node (ref "U1") (pin "46") (pinfunction "DRDY_46") (pintype "output"))
    )
    (net (code "15") (name "/FPATH") (class "Default")
      (node (ref "R21") (pin "1") (pinfunction "1_1") (pintype "passive"))
      (node (ref "R28") (pin "1") (pinfunction "1_1") (pintype "passive"))
      (node (ref "U1") (pin "33") (pinfunction "FPATH_33") (pintype "input"))
    )
    (net (code "16") (name "/LL_CONFIG") (class "Default")
      (node (ref "R22") (pin "1") (pinfunction "1_1") (pintype "passive"))
      (node (ref "R29") (pin "2") (pinfunction "2_2") (pintype "passive"))
      (node (ref "U1") (pin "32") (pinfunction "LL_CONFIG_32") (pintype "input"))
    )
    (net (code "17") (name "/LVDS") (class "Default")
      (node (ref "L5") (pin "2") (pinfunction "2_2") (pintype "passive"))
      (node (ref "R21") (pin "2") (pinfunction "2_2") (pintype "passive"))
      (node (ref "R22") (pin "2") (pinfunction "2_2") (pintype "passive"))
      (node (ref "R23") (pin "2") (pinfunction "2_2") (pintype "passive"))
      (node (ref "R24") (pin "2") (pinfunction "2_2") (pintype "passive"))
      (node (ref "R25") (pin "2") (pinfunction "2_2") (pintype "passive"))
      (node (ref "U1") (pin "28") (pinfunction "~{PDWN}_28") (pintype "input"))
      (node (ref "U1") (pin "29") (pinfunction "SCLK_SEL_29") (pintype "input"))
      (node (ref "U1") (pin "30") (pinfunction "~{LVDS}_30") (pintype "input"))
    )
    (net (code "18") (name "/REF_BUFFER") (class "Default")
      (node (ref "C18") (pin "2") (pinfunction "A_2") (pintype "passive"))
      (node (ref "C19") (pin "2") (pinfunction "A_2") (pintype "passive"))
      (node (ref "C20") (pin "1") (pinfunction "1_1") (pintype "passive"))
      (node (ref "R17") (pin "1") (pinfunction "1_1") (pintype "passive"))
      (node (ref "U12") (pin "3") (pinfunction "IN+_3") (pintype "input"))
    )
    (net (code "19") (name "/Ref_2.5") (class "Default")
      (node (ref "R41") (pin "1") (pinfunction "1_1") (pintype "passive"))
      (node (ref "U13") (pin "3") (pinfunction "IN_A+_3") (pintype "input"))
      (node (ref "U13") (pin "5") (pinfunction "IN_B+_5") (pintype "input"))
    )
    (net (code "20") (name "/SCLK_AD") (class "Default")
      (node (ref "R34") (pin "2") (pinfunction "2_2") (pintype "passive"))
      (node (ref "U1") (pin "42") (pinfunction "SCLK_42") (pintype "bidirectional"))
    )
    (net (code "21") (name "/START_AD") (class "Default")
      (node (ref "R38") (pin "2") (pinfunction "2_2") (pintype "passive"))
      (node (ref "U1") (pin "37") (pinfunction "START_37") (pintype "input"))
    )
    (net (code "22") (name "/VREFP") (class "Default")
      (node (ref "C37") (pin "2") (pinfunction "A_2") (pintype "passive"))
      (node (ref "C38") (pin "2") (pinfunction "A_2") (pintype "passive"))
      (node (ref "C39") (pin "2") (pinfunction "A_2") (pintype "passive"))
      (node (ref "C40") (pin "1") (pinfunction "1_1") (pintype "passive"))
      (node (ref "R18") (pin "1") (pinfunction "1_1") (pintype "passive"))
      (node (ref "R26") (pin "1") (pinfunction "1_1") (pintype "passive"))
      (node (ref "U1") (pin "63") (pinfunction "VREFP_63") (pintype "input"))
      (node (ref "U1") (pin "64") (pinfunction "VREFP_64") (pintype "input"))
    )
    (net (code "23") (name "GND") (class "Default")
      (node (ref "C10") (pin "2") (pinfunction "2_2") (pintype "passive"))
      (node (ref "C11") (pin "2") (pinfunction "2_2") (pintype "passive"))
      (node (ref "C14") (pin "2") (pinfunction "2_2") (pintype "passive"))
      (node (ref "C15") (pin "2") (pinfunction "2_2") (pintype "passive"))
      (node (ref "C16") (pin "1") (pinfunction "C_1") (pintype "passive"))
      (node (ref "C17") (pin "1") (pinfunction "C_1") (pintype "passive"))
      (node (ref "C18") (pin "1") (pinfunction "C_1") (pintype "passive"))
      (node (ref "C19") (pin "1") (pinfunction "C_1") (pintype "passive"))
      (node (ref "C2") (pin "2") (pinfunction "2_2") (pintype "passive"))
      (node (ref "C20") (pin "2") (pinfunction "2_2") (pintype "passive"))
      (node (ref "C21") (pin "2") (pinfunction "2_2") (pintype "passive"))
      (node (ref "C22") (pin "2") (pinfunction "2_2") (pintype "passive"))
      (node (ref "C23") (pin "2") (pinfunction "2_2") (pintype "passive"))
      (node (ref "C24") (pin "2") (pinfunction "2_2") (pintype "passive"))
      (node (ref "C25") (pin "2") (pinfunction "2_2") (pintype "passive"))
      (node (ref "C26") (pin "2") (pinfunction "2_2") (pintype "passive"))
      (node (ref "C27") (pin "2") (pinfunction "2_2") (pintype "passive"))
      (node (ref "C3") (pin "2") (pinfunction "2_2") (pintype "passive"))
      (node (ref "C34") (pin "2") (pinfunction "2_2") (pintype "passive"))
      (node (ref "C35") (pin "2") (pinfunction "2_2") (pintype "passive"))
      (node (ref "C36") (pin "2") (pinfunction "2_2") (pintype "passive"))
      (node (ref "C37") (pin "1") (pinfunction "C_1") (pintype "passive"))
      (node (ref "C38") (pin "1") (pinfunction "C_1") (pintype "passive"))
      (node (ref "C39") (pin "1") (pinfunction "C_1") (pintype "passive"))
      (node (ref "C4") (pin "2") (pinfunction "2_2") (pintype "passive"))
      (node (ref "C40") (pin "2") (pinfunction "2_2") (pintype "passive"))
      (node (ref "C43") (pin "2") (pinfunction "2_2") (pintype "passive"))
      (node (ref "C44") (pin "2") (pinfunction "2_2") (pintype "passive"))
      (node (ref "C45") (pin "2") (pinfunction "2_2") (pintype "passive"))
      (node (ref "C46") (pin "1") (pinfunction "1_1") (pintype "passive"))
      (node (ref "C48") (pin "2") (pinfunction "2_2") (pintype "passive"))
      (node (ref "C49") (pin "2") (pinfunction "2_2") (pintype "passive"))
      (node (ref "C5") (pin "2") (pinfunction "2_2") (pintype "passive"))
      (node (ref "C50") (pin "2") (pinfunction "2_2") (pintype "passive"))
      (node (ref "C51") (pin "1") (pinfunction "1_1") (pintype "passive"))
      (node (ref "C52") (pin "2") (pinfunction "2_2") (pintype "passive"))
      (node (ref "C53") (pin "2") (pinfunction "2_2") (pintype "passive"))
      (node (ref "C54") (pin "2") (pinfunction "2_2") (pintype "passive"))
      (node (ref "C55") (pin "2") (pinfunction "2_2") (pintype "passive"))
      (node (ref "C56") (pin "2") (pinfunction "2_2") (pintype "passive"))
      (node (ref "C6") (pin "2") (pinfunction "2_2") (pintype "passive"))
      (node (ref "C7") (pin "2") (pinfunction "2_2") (pintype "passive"))
      (node (ref "C8") (pin "2") (pinfunction "2_2") (pintype "passive"))
      (node (ref "C9") (pin "2") (pinfunction "2_2") (pintype "passive"))
      (node (ref "PD") (pin "S") (pinfunction "S_S") (pintype "passive"))
      (node (ref "R28") (pin "2") (pinfunction "2_2") (pintype "passive"))
      (node (ref "R29") (pin "1") (pinfunction "1_1") (pintype "passive"))
      (node (ref "R30") (pin "2") (pinfunction "2_2") (pintype "passive"))
      (node (ref "R31") (pin "1") (pinfunction "1_1") (pintype "passive"))
      (node (ref "R32") (pin "1") (pinfunction "1_1") (pintype "passive"))
      (node (ref "R37") (pin "2") (pinfunction "2_2") (pintype "passive"))
      (node (ref "U1") (pin "10") (pinfunction "AGND_10") (pintype "power_in"))
      (node (ref "U1") (pin "14") (pinfunction "DGND_14") (pintype "power_in"))
      (node (ref "U1") (pin "15") (pinfunction "DGND_15") (pintype "power_in"))
      (node (ref "U1") (pin "16") (pinfunction "DGND_16") (pintype "power_in"))
      (node (ref "U1") (pin "17") (pinfunction "DGND_17") (pintype "power_in"))
      (node (ref "U1") (pin "18") (pinfunction "DGND_18") (pintype "power_in"))
      (node (ref "U1") (pin "19") (pinfunction "DGND_19") (pintype "power_in"))
      (node (ref "U1") (pin "2") (pinfunction "AGND_2") (pintype "power_in"))
      (node (ref "U1") (pin "20") (pinfunction "DGND_20") (pintype "power_in"))
      (node (ref "U1") (pin "21") (pinfunction "RSV2_21") (pintype "passive"))
      (node (ref "U1") (pin "22") (pinfunction "RSV1_22") (pintype "passive"))
      (node (ref "U1") (pin "25") (pinfunction "DGND_25") (pintype "power_in"))
      (node (ref "U1") (pin "26") (pinfunction "DGND_26") (pintype "power_in"))
      (node (ref "U1") (pin "3") (pinfunction "AGND_3") (pintype "power_in"))
      (node (ref "U1") (pin "31") (pinfunction "DGND_31") (pintype "power_in"))
      (node (ref "U1") (pin "47") (pinfunction "DGND_47") (pintype "power_in"))
      (node (ref "U1") (pin "50") (pinfunction "DGND_50") (pintype "power_in"))
      (node (ref "U1") (pin "51") (pinfunction "DGND_51") (pintype "power_in"))
      (node (ref "U1") (pin "54") (pinfunction "AGND_54") (pintype "power_in"))
      (node (ref "U1") (pin "56") (pinfunction "AGND_56") (pintype "power_in"))
      (node (ref "U1") (pin "57") (pinfunction "AGND_57") (pintype "power_in"))
      (node (ref "U1") (pin "6") (pinfunction "AGND_6") (pintype "power_in"))
      (node (ref "U1") (pin "60") (pinfunction "VREFN_60") (pintype "input"))
      (node (ref "U1") (pin "61") (pinfunction "VREFN_61") (pintype "input"))
      (node (ref "U1") (pin "9") (pinfunction "AGND_9") (pintype "power_in"))
      (node (ref "U11") (pin "4") (pinfunction "GND_4") (pintype "power_in"))
      (node (ref "U12") (pin "4") (pinfunction "V-_4") (pintype "power_in"))
      (node (ref "U12") (pin "8") (pinfunction "SHUTDOWN_8") (pintype "input"))
      (node (ref "U13") (pin "4") (pinfunction "V-_4") (pintype "power_in"))
      (node (ref "U14") (pin "4") (pinfunction "GND_4") (pintype "power_in"))
    )
    (net (code "24") (name "Net-(C16-A)") (class "Default")
      (node (ref "C16") (pin "2") (pinfunction "A_2") (pintype "passive"))
      (node (ref "U11") (pin "5") (pinfunction "TRIM_5") (pintype "input"))
    )
    (net (code "25") (name "Net-(C17-A)") (class "Default")
      (node (ref "C17") (pin "2") (pinfunction "A_2") (pintype "passive"))
      (node (ref "R17") (pin "2") (pinfunction "2_2") (pintype "passive"))
      (node (ref "U11") (pin "6") (pinfunction "VOUT_6") (pintype "power_in"))
    )
    (net (code "26") (name "Net-(C21-Pad1)") (class "Default")
      (node (ref "C21") (pin "1") (pinfunction "1_1") (pintype "passive"))
      (node (ref "C22") (pin "1") (pinfunction "1_1") (pintype "passive"))
      (node (ref "C23") (pin "1") (pinfunction "1_1") (pintype "passive"))
      (node (ref "C24") (pin "1") (pinfunction "1_1") (pintype "passive"))
      (node (ref "C25") (pin "1") (pinfunction "1_1") (pintype "passive"))
      (node (ref "C26") (pin "1") (pinfunction "1_1") (pintype "passive"))
      (node (ref "C27") (pin "1") (pinfunction "1_1") (pintype "passive"))
      (node (ref "L3") (pin "2") (pinfunction "2_2") (pintype "passive"))
      (node (ref "L4") (pin "1") (pinfunction "1_1") (pintype "passive"))
      (node (ref "U1") (pin "23") (pinfunction "DVDD_23") (pintype "power_in"))
      (node (ref "U1") (pin "24") (pinfunction "DVDD_24") (pintype "power_in"))
      (node (ref "U1") (pin "27") (pinfunction "DVDD_27") (pintype "power_in"))
      (node (ref "U1") (pin "48") (pinfunction "DVDD_48") (pintype "power_in"))
      (node (ref "U1") (pin "49") (pinfunction "DVDD_49") (pintype "power_in"))
      (node (ref "U1") (pin "52") (pinfunction "DVDD_52") (pintype "power_in"))
    )
    (net (code "27") (name "Net-(C36-Pad1)") (class "Default")
      (node (ref "C36") (pin "1") (pinfunction "1_1") (pintype "passive"))
      (node (ref "R19") (pin "1") (pinfunction "1_1") (pintype "passive"))
      (node (ref "R20") (pin "2") (pinfunction "2_2") (pintype "passive"))
    )
    (net (code "28") (name "Net-(C41-Pad2)") (class "Default")
      (node (ref "C41") (pin "2") (pinfunction "2_2") (pintype "passive"))
      (node (ref "C42") (pin "1") (pinfunction "1_1") (pintype "passive"))
    )
    (net (code "29") (name "Net-(C49-Pad1)") (class "Default")
      (node (ref "C49") (pin "1") (pinfunction "1_1") (pintype "passive"))
      (node (ref "R39") (pin "1") (pinfunction "1_1") (pintype "passive"))
      (node (ref "R40") (pin "2") (pinfunction "2_2") (pintype "passive"))
    )
    (net (code "30") (name "Net-(C57-Pad2)") (class "Default")
      (node (ref "C57") (pin "2") (pinfunction "2_2") (pintype "passive"))
      (node (ref "C58") (pin "1") (pinfunction "1_1") (pintype "passive"))
    )
    (net (code "31") (name "Net-(U1A-CAP1)") (class "Default")
      (node (ref "C51") (pin "2") (pinfunction "2_2") (pintype "passive"))
      (node (ref "U1") (pin "59") (pinfunction "CAP1_59") (pintype "passive"))
    )
    (net (code "32") (name "Net-(U1A-CAP2)") (class "Default")
      (node (ref "C50") (pin "1") (pinfunction "1_1") (pintype "passive"))
      (node (ref "U1") (pin "62") (pinfunction "CAP2_62") (pintype "passive"))
    )
    (net (code "33") (name "Net-(U1A-RBIAS)") (class "Default")
      (node (ref "R37") (pin "1") (pinfunction "1_1") (pintype "passive"))
      (node (ref "U1") (pin "8") (pinfunction "RBIAS_8") (pintype "passive"))
    )
    (net (code "34") (name "Net-(U1A-VCM)") (class "Default")
      (node (ref "C46") (pin "2") (pinfunction "2_2") (pintype "passive"))
      (node (ref "U1") (pin "13") (pinfunction "VCM_13") (pintype "output"))
    )
    (net (code "35") (name "Net-(U12-IN-)") (class "Default")
      (node (ref "C33") (pin "1") (pinfunction "1_1") (pintype "passive"))
      (node (ref "R18") (pin "2") (pinfunction "2_2") (pintype "passive"))
      (node (ref "U12") (pin "2") (pinfunction "IN-_2") (pintype "input"))
    )
    (net (code "36") (name "Net-(U12-OUT)") (class "Default")
      (node (ref "C33") (pin "2") (pinfunction "2_2") (pintype "passive"))
      (node (ref "R26") (pin "2") (pinfunction "2_2") (pintype "passive"))
      (node (ref "U12") (pin "6") (pinfunction "OUT_6") (pintype "tri_state"))
    )
    (net (code "37") (name "Net-(U13A-IN_A-)") (class "Default")
      (node (ref "C41") (pin "1") (pinfunction "1_1") (pintype "passive"))
      (node (ref "PD") (pin "K") (pinfunction "K_K") (pintype "output"))
      (node (ref "R19") (pin "2") (pinfunction "2_2") (pintype "passive"))
      (node (ref "R27") (pin "2") (pinfunction "2_2") (pintype "passive"))
      (node (ref "U13") (pin "2") (pinfunction "IN_A-_2") (pintype "input"))
    )
    (net (code "38") (name "Net-(U13A-OUT_A)") (class "Default")
      (node (ref "C42") (pin "2") (pinfunction "2_2") (pintype "passive"))
      (node (ref "R20") (pin "1") (pinfunction "1_1") (pintype "passive"))
      (node (ref "R27") (pin "1") (pinfunction "1_1") (pintype "passive"))
      (node (ref "R33") (pin "2") (pinfunction "2_2") (pintype "passive"))
      (node (ref "U13") (pin "1") (pinfunction "OUT_A_1") (pintype "output"))
    )
    (net (code "39") (name "Net-(U13B-IN_B-)") (class "Default")
      (node (ref "C57") (pin "1") (pinfunction "1_1") (pintype "passive"))
      (node (ref "PD") (pin "A") (pinfunction "A_A") (pintype "input"))
      (node (ref "R39") (pin "2") (pinfunction "2_2") (pintype "passive"))
      (node (ref "R42") (pin "2") (pinfunction "2_2") (pintype "passive"))
      (node (ref "U13") (pin "6") (pinfunction "IN_B-_6") (pintype "input"))
    )
    (net (code "40") (name "Net-(U13B-OUT_B)") (class "Default")
      (node (ref "C58") (pin "2") (pinfunction "2_2") (pintype "passive"))
      (node (ref "R36") (pin "2") (pinfunction "2_2") (pintype "passive"))
      (node (ref "R40") (pin "1") (pinfunction "1_1") (pintype "passive"))
      (node (ref "R42") (pin "1") (pinfunction "1_1") (pintype "passive"))
      (node (ref "U13") (pin "7") (pinfunction "OUT_B_7") (pintype "output"))
    )
    (net (code "41") (name "Net-(U14A-TRIM)") (class "Default")
      (node (ref "C56") (pin "1") (pinfunction "1_1") (pintype "passive"))
      (node (ref "U14") (pin "5") (pinfunction "TRIM_5") (pintype "input"))
    )
    (net (code "42") (name "Net-(U14A-VOUT)") (class "Default")
      (node (ref "C54") (pin "1") (pinfunction "1_1") (pintype "passive"))
      (node (ref "C55") (pin "1") (pinfunction "1_1") (pintype "passive"))
      (node (ref "R41") (pin "2") (pinfunction "2_2") (pintype "passive"))
      (node (ref "U14") (pin "6") (pinfunction "VOUT_6") (pintype "power_in"))
    )
    (net (code "43") (name "unconnected-(U1A-OTRA-Pad40)") (class "Default")
      (node (ref "U1") (pin "40") (pinfunction "OTRA_40") (pintype "output+no_connect"))
    )
    (net (code "44") (name "unconnected-(U1A-OTRD-Pad39)") (class "Default")
      (node (ref "U1") (pin "39") (pinfunction "OTRD_39") (pintype "output+no_connect"))
    )
    (net (code "45") (name "unconnected-(U1A-~{DOUT}-Pad43)") (class "Default")
      (node (ref "U1") (pin "43") (pinfunction "~{DOUT}_43") (pintype "tri_state+no_connect"))
    )
    (net (code "46") (name "unconnected-(U1A-~{DRDY}-Pad45)") (class "Default")
      (node (ref "U1") (pin "45") (pinfunction "~{DRDY}_45") (pintype "output+no_connect"))
    )
    (net (code "47") (name "unconnected-(U1A-~{SCLK}-Pad41)") (class "Default")
      (node (ref "U1") (pin "41") (pinfunction "~{SCLK}_41") (pintype "tri_state+no_connect"))
    )
    (net (code "48") (name "unconnected-(U12-NC-Pad1)") (class "Default")
      (node (ref "U12") (pin "1") (pinfunction "NC_1") (pintype "passive+no_connect"))
    )
    (net (code "49") (name "unconnected-(U12-NC-Pad5)") (class "Default")
      (node (ref "U12") (pin "5") (pinfunction "NC_5") (pintype "passive+no_connect"))
    )
    (net (code "50") (name "unconnected-(U13B-V+-Pad8)") (class "Default")
      (node (ref "U13") (pin "8") (pinfunction "V+_8") (pintype "power_in"))
    )
    (net (code "51") (name "unconnected-(U13B-V--Pad4)") (class "Default")
      (node (ref "U13") (pin "4") (pinfunction "V-_4") (pintype "power_in"))
    )
  )
)
